# LPCB220_-_WATCHDOG.net
KiCad netlist of a schematic drawn in Altium Designer
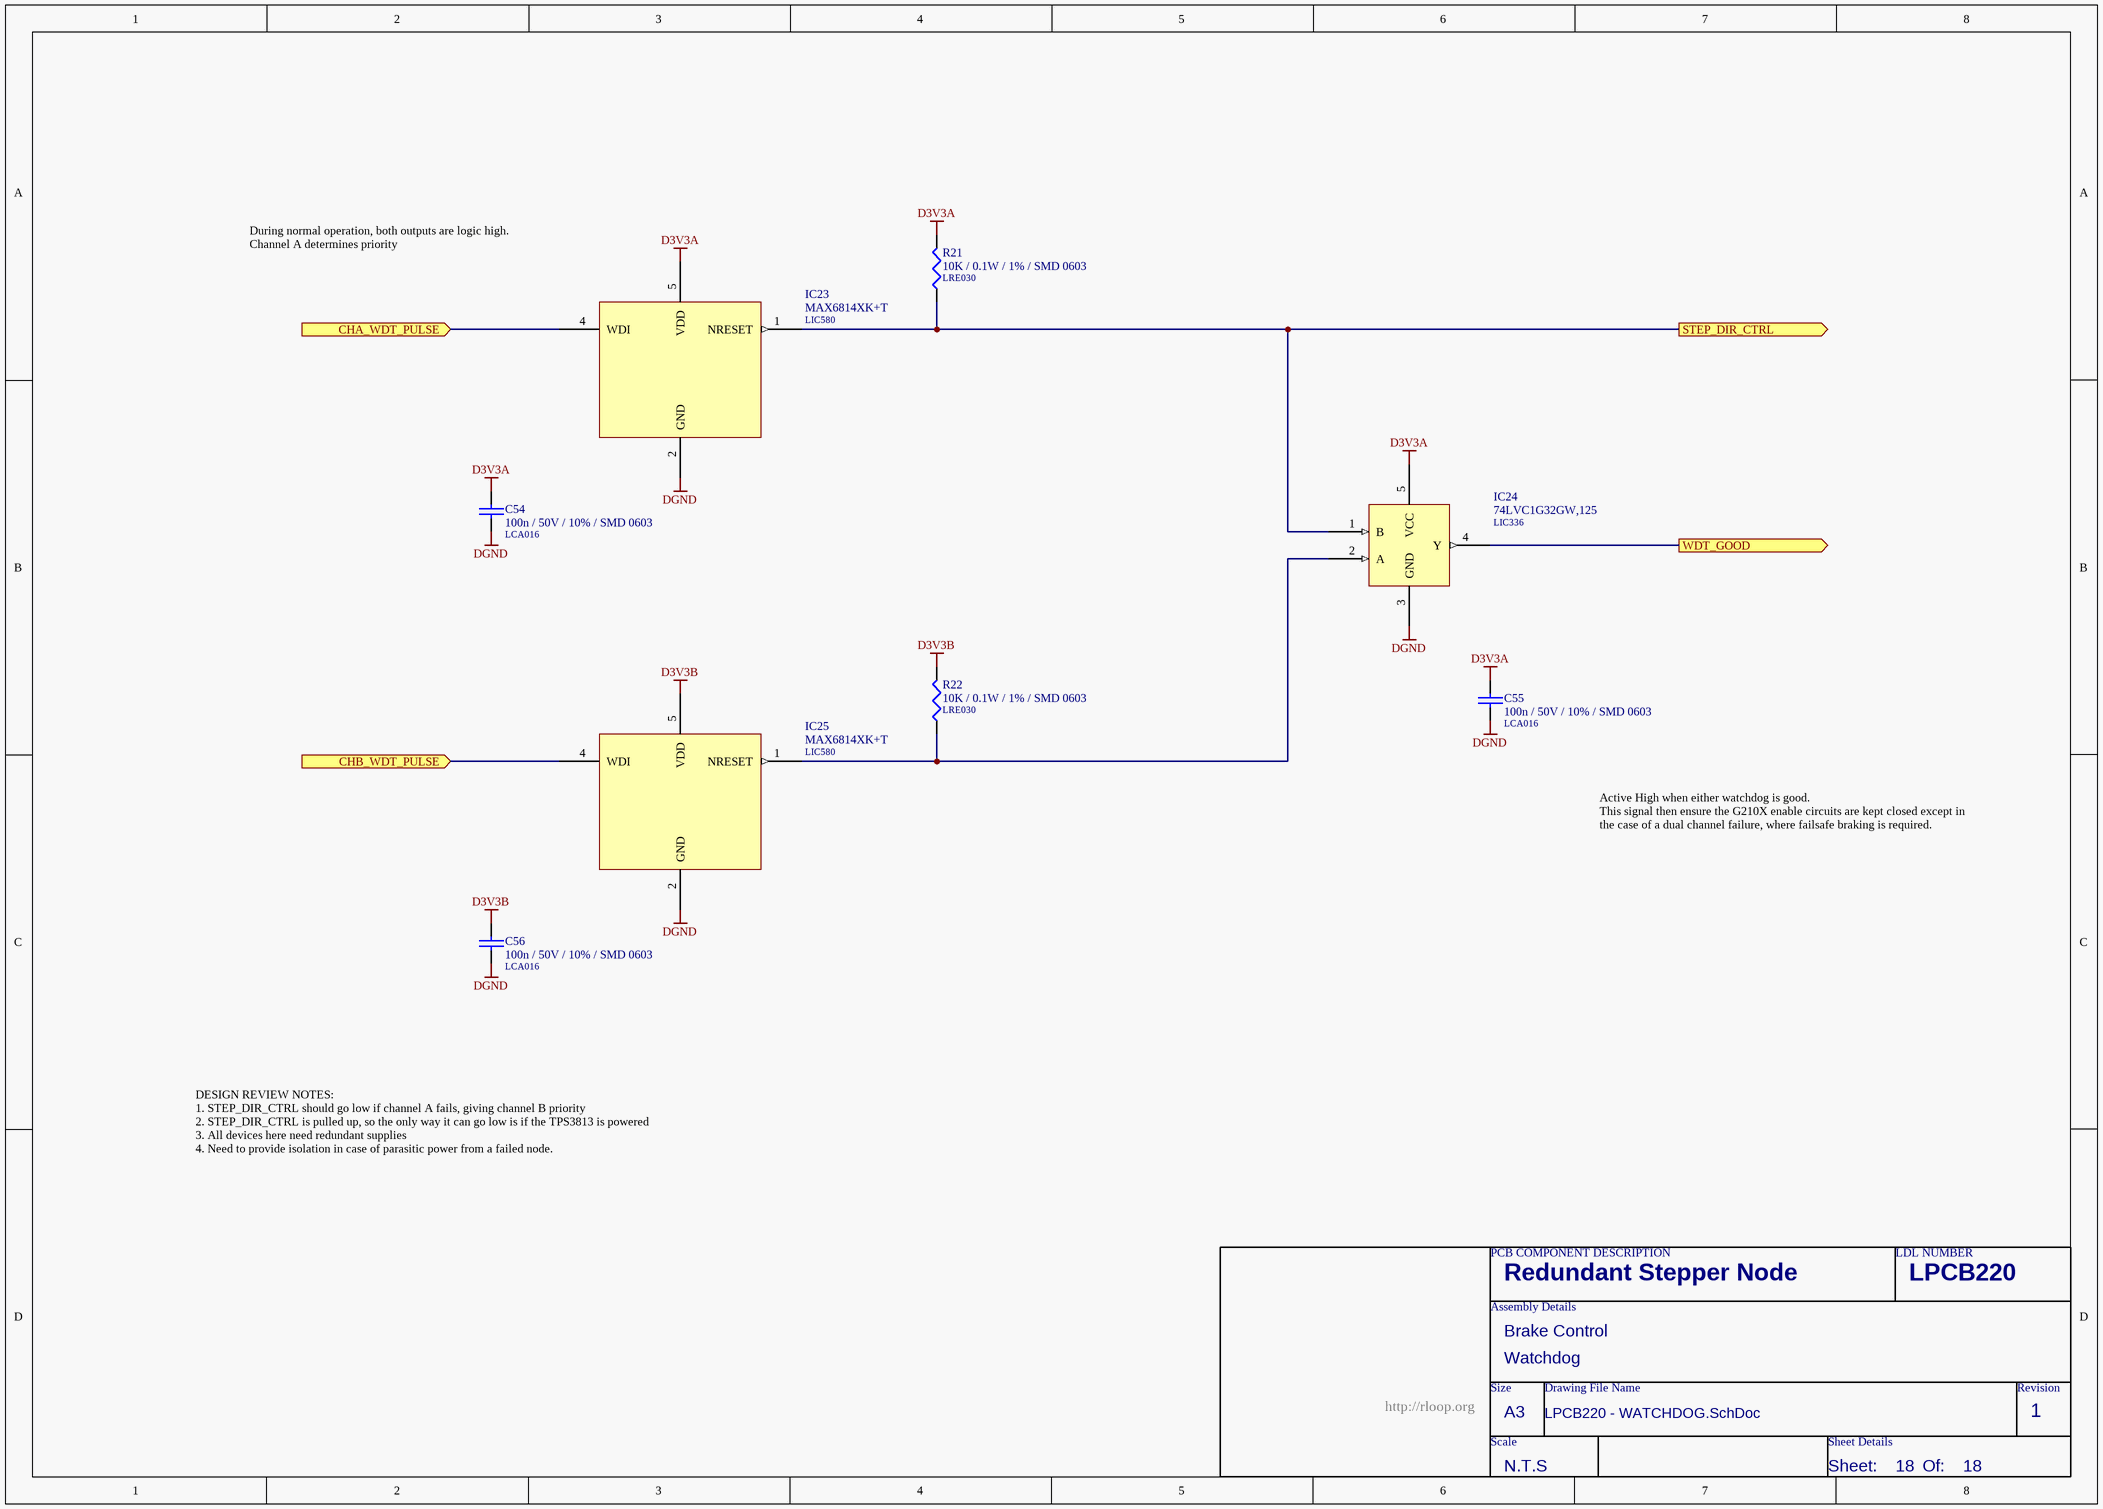
[diagram p0: LPCB220 - WATCHDOG.SchDoc]

(export (version "E")
  (design (tool "Eeschema 10.0.6"))
  (components
    (comp (ref "C54")
      (value "100n / 50V / 10% / SMD 0603")
      (footprint "LFP011__CC1608-0603-IPC7351_B")
      (description "Capacitor, Ceramic Chip, 100nF (0.1uF), 50V, 5%, SMD 0603 [LCA016]")
      (fields (field (name "LDL_NUMBER") "LCA016"))
      (libsource (lib "LDL_Capacitors") (part "100n / 50V / 10% / SMD 0603"))
    )
    (comp (ref "C55")
      (value "100n / 50V / 10% / SMD 0603")
      (footprint "LFP011__CC1608-0603-IPC7351_B")
      (description "Capacitor, Ceramic Chip, 100nF (0.1uF), 50V, 5%, SMD 0603 [LCA016]")
      (fields (field (name "LDL_NUMBER") "LCA016"))
      (libsource (lib "LDL_Capacitors") (part "100n / 50V / 10% / SMD 0603"))
    )
    (comp (ref "C56")
      (value "100n / 50V / 10% / SMD 0603")
      (footprint "LFP011__CC1608-0603-IPC7351_B")
      (description "Capacitor, Ceramic Chip, 100nF (0.1uF), 50V, 5%, SMD 0603 [LCA016]")
      (fields (field (name "LDL_NUMBER") "LCA016"))
      (libsource (lib "LDL_Capacitors") (part "100n / 50V / 10% / SMD 0603"))
    )
    (comp (ref "IC23")
      (value "MAX6814XK+T")
      (footprint "LFP047__SOT353")
      (description "IC, Watchdog, SMD [LIC580]")
      (fields (field (name "LDL_NUMBER") "LIC580"))
      (libsource (lib "LDL_Semiconductors") (part "MAX6814XK+T"))
    )
    (comp (ref "IC24")
      (value "74LVC1G32GW,125")
      (footprint "LFP047__SOT353")
      (description "IC, Logic OR Gate, Single 2 Input, SMD SOT353 [LIC336]")
      (fields (field (name "LDL_NUMBER") "LIC336"))
      (libsource (lib "LDL_Semiconductors") (part "74LVC1G32GW,125"))
    )
    (comp (ref "IC25")
      (value "MAX6814XK+T")
      (footprint "LFP047__SOT353")
      (description "IC, Watchdog, SMD [LIC580]")
      (fields (field (name "LDL_NUMBER") "LIC580"))
      (libsource (lib "LDL_Semiconductors") (part "MAX6814XK+T"))
    )
    (comp (ref "R21")
      (value "10K / 0.1W / 1% / SMD 0603")
      (footprint "LFP020__CR1608-0603-IPC7351_B")
      (description "Resistor, Ceramic Chip, 10K, 0.1W, 1%, SMD 0603 [LRE030]")
      (fields (field (name "LDL_NUMBER") "LRE030"))
      (libsource (lib "LDL_Resistors") (part "10K / 0.1W / 1% / SMD 0603"))
    )
    (comp (ref "R22")
      (value "10K / 0.1W / 1% / SMD 0603")
      (footprint "LFP020__CR1608-0603-IPC7351_B")
      (description "Resistor, Ceramic Chip, 10K, 0.1W, 1%, SMD 0603 [LRE030]")
      (fields (field (name "LDL_NUMBER") "LRE030"))
      (libsource (lib "LDL_Resistors") (part "10K / 0.1W / 1% / SMD 0603"))
    )
  )
  (nets
    (net (code "1") (name "/CHA_WDT_PULSE") (class "Default")
      (node (ref "IC23") (pin "4") (pinfunction "WDI_4") (pintype "passive"))
    )
    (net (code "2") (name "/CHB_WDT_PULSE") (class "Default")
      (node (ref "IC25") (pin "4") (pinfunction "WDI_4") (pintype "passive"))
    )
    (net (code "3") (name "/STEP_DIR_CTRL") (class "Default")
      (node (ref "IC23") (pin "1") (pinfunction "NRESET_1") (pintype "output"))
      (node (ref "IC24") (pin "1") (pinfunction "B_1") (pintype "input"))
      (node (ref "R21") (pin "1") (pintype "passive"))
    )
    (net (code "4") (name "/WDT_GOOD") (class "Default")
      (node (ref "IC24") (pin "4") (pinfunction "Y_4") (pintype "output"))
    )
    (net (code "5") (name "D3V3A") (class "Default")
      (node (ref "C54") (pin "1") (pintype "passive"))
      (node (ref "C55") (pin "1") (pintype "passive"))
      (node (ref "IC23") (pin "5") (pinfunction "VDD_5") (pintype "power_in"))
      (node (ref "IC24") (pin "5") (pinfunction "VCC_5") (pintype "power_in"))
      (node (ref "R21") (pin "2") (pintype "passive"))
    )
    (net (code "6") (name "D3V3B") (class "Default")
      (node (ref "C56") (pin "1") (pintype "passive"))
      (node (ref "IC25") (pin "5") (pinfunction "VDD_5") (pintype "power_in"))
      (node (ref "R22") (pin "2") (pintype "passive"))
    )
    (net (code "7") (name "DGND") (class "Default")
      (node (ref "C54") (pin "2") (pintype "passive"))
      (node (ref "C55") (pin "2") (pintype "passive"))
      (node (ref "C56") (pin "2") (pintype "passive"))
      (node (ref "IC23") (pin "2") (pinfunction "GND_2") (pintype "power_in"))
      (node (ref "IC24") (pin "3") (pinfunction "GND_3") (pintype "power_in"))
      (node (ref "IC25") (pin "2") (pinfunction "GND_2") (pintype "power_in"))
    )
    (net (code "8") (name "Net-(IC24-A)") (class "Default")
      (node (ref "IC24") (pin "2") (pinfunction "A_2") (pintype "input"))
      (node (ref "IC25") (pin "1") (pinfunction "NRESET_1") (pintype "output"))
      (node (ref "R22") (pin "1") (pintype "passive"))
    )
  )
)
